# Effects.net
KiCad netlist of a schematic drawn in Altium Designer
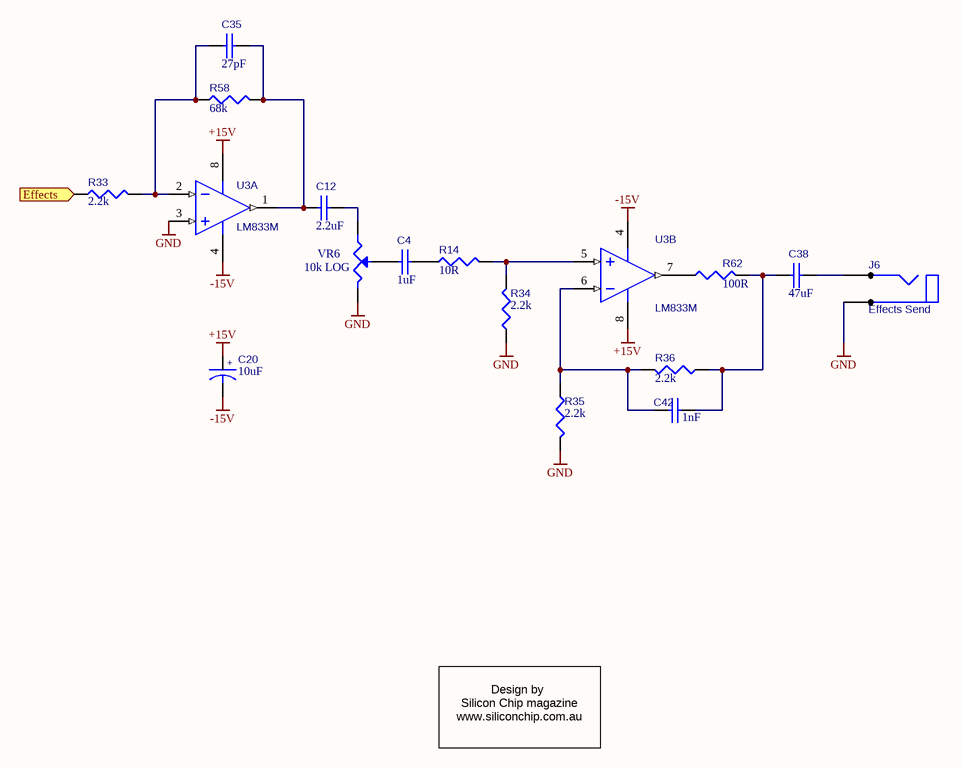
[diagram p0: Effects.SchDoc]

(export (version "E")
  (design (tool "Eeschema 10.0.6"))
  (components
    (comp (ref "C4")
      (value "1uF")
      (footprint "RB.2/.4-NP")
      (description "Capacitor")
      (libsource (lib "*") (part "CAP"))
    )
    (comp (ref "C12")
      (value "2.2uF")
      (footprint "RB.2/.4-NP")
      (description "Capacitor")
      (libsource (lib "*") (part "CAP"))
    )
    (comp (ref "C20")
      (value "10uF")
      (footprint "RB.2/.4")
      (description "Bi-Polar Capacitor")
      (libsource (lib "*") (part "CAPACITOR POL"))
    )
    (comp (ref "C35")
      (value "27pF")
      (footprint "RAD0.2")
      (description "Capacitor")
      (libsource (lib "*") (part "CAP"))
    )
    (comp (ref "C38")
      (value "47uF")
      (footprint "RB.2/.4-NP")
      (description "Capacitor")
      (libsource (lib "*") (part "CAP"))
    )
    (comp (ref "C42")
      (value "1nF")
      (footprint "RAD0.2")
      (description "Capacitor")
      (libsource (lib "*") (part "CAP"))
    )
    (comp (ref "J6")
      (value "Effects Send")
      (footprint "JACK-6.25MM")
      (libsource (lib "*") (part "PHONEJACK MONO"))
    )
    (comp (ref "R14")
      (value "10R")
      (footprint "AXIAL0.4")
      (description "Resistor")
      (libsource (lib "*") (part "RES1"))
    )
    (comp (ref "R33")
      (value "2.2k")
      (footprint "AXIAL0.4")
      (description "Resistor")
      (libsource (lib "*") (part "RES1"))
    )
    (comp (ref "R34")
      (value "2.2k")
      (footprint "AXIAL0.4")
      (description "Resistor")
      (libsource (lib "") (part "RES1_2"))
    )
    (comp (ref "R35")
      (value "2.2k")
      (footprint "AXIAL0.4")
      (description "Resistor")
      (libsource (lib "") (part "RES1_3"))
    )
    (comp (ref "R36")
      (value "2.2k")
      (footprint "AXIAL0.4")
      (description "Resistor")
      (libsource (lib "") (part "RES1_1"))
    )
    (comp (ref "R58")
      (value "68k")
      (footprint "AXIAL0.4")
      (description "Resistor")
      (libsource (lib "*") (part "RES1"))
    )
    (comp (ref "R62")
      (value "100R")
      (footprint "AXIAL0.4")
      (description "Resistor")
      (libsource (lib "*") (part "RES1"))
    )
    (comp (ref "U3")
      (value "LM833M")
      (footprint "DIP8")
      (description "Fast Settling Dual Operational Amplifier")
      (libsource (lib "*") (part "LM833M"))
    )
    (comp (ref "VR6")
      (value "10k LOG")
      (footprint "POT - 24MM")
      (description "Potentiometer")
      (libsource (lib "*") (part "POT1"))
    )
  )
  (nets
    (net (code "1") (name "+15V") (class "Default")
      (node (ref "C20") (pin "1") (pinfunction "1_1") (pintype "passive"))
      (node (ref "U3") (pin "8") (pinfunction "V+_8") (pintype "power_in"))
    )
    (net (code "2") (name "-15V") (class "Default")
      (node (ref "C20") (pin "2") (pinfunction "2_2") (pintype "passive"))
      (node (ref "U3") (pin "4") (pinfunction "V-_4") (pintype "power_in"))
    )
    (net (code "3") (name "/Effects") (class "Default")
      (node (ref "R33") (pin "1") (pinfunction "1_1") (pintype "passive"))
    )
    (net (code "4") (name "GND") (class "Default")
      (node (ref "J6") (pin "3") (pinfunction "C_3") (pintype "passive"))
      (node (ref "R34") (pin "1") (pinfunction "1_1") (pintype "passive"))
      (node (ref "R35") (pin "2") (pinfunction "2_2") (pintype "passive"))
      (node (ref "U3") (pin "3") (pinfunction "IN1+_3") (pintype "input"))
      (node (ref "VR6") (pin "3") (pinfunction "3_3") (pintype "passive"))
    )
    (net (code "5") (name "Net-(C4-Pad2)") (class "Default")
      (node (ref "C4") (pin "2") (pinfunction "2_2") (pintype "passive"))
      (node (ref "R14") (pin "1") (pinfunction "1_1") (pintype "passive"))
    )
    (net (code "6") (name "Net-(C12-Pad2)") (class "Default")
      (node (ref "C12") (pin "2") (pinfunction "2_2") (pintype "passive"))
      (node (ref "VR6") (pin "1") (pinfunction "1_1") (pintype "passive"))
    )
    (net (code "7") (name "Net-(C38-Pad1)") (class "Default")
      (node (ref "C38") (pin "1") (pinfunction "1_1") (pintype "passive"))
      (node (ref "C42") (pin "2") (pinfunction "2_2") (pintype "passive"))
      (node (ref "R36") (pin "1") (pinfunction "1_1") (pintype "passive"))
      (node (ref "R62") (pin "2") (pinfunction "2_2") (pintype "passive"))
    )
    (net (code "8") (name "Net-(J6-A)") (class "Default")
      (node (ref "C38") (pin "2") (pinfunction "2_2") (pintype "passive"))
      (node (ref "J6") (pin "1") (pinfunction "A_1") (pintype "passive"))
    )
    (net (code "9") (name "Net-(U3A-IN1-)") (class "Default")
      (node (ref "C35") (pin "1") (pinfunction "1_1") (pintype "passive"))
      (node (ref "R33") (pin "2") (pinfunction "2_2") (pintype "passive"))
      (node (ref "R58") (pin "1") (pinfunction "1_1") (pintype "passive"))
      (node (ref "U3") (pin "2") (pinfunction "IN1-_2") (pintype "input"))
    )
    (net (code "10") (name "Net-(U3A-OUT1)") (class "Default")
      (node (ref "C12") (pin "1") (pinfunction "1_1") (pintype "passive"))
      (node (ref "C35") (pin "2") (pinfunction "2_2") (pintype "passive"))
      (node (ref "R58") (pin "2") (pinfunction "2_2") (pintype "passive"))
      (node (ref "U3") (pin "1") (pinfunction "OUT1_1") (pintype "output"))
    )
    (net (code "11") (name "Net-(U3B-IN2+)") (class "Default")
      (node (ref "R14") (pin "2") (pinfunction "2_2") (pintype "passive"))
      (node (ref "R34") (pin "2") (pinfunction "2_2") (pintype "passive"))
      (node (ref "U3") (pin "5") (pinfunction "IN2+_5") (pintype "input"))
    )
    (net (code "12") (name "Net-(U3B-IN2-)") (class "Default")
      (node (ref "C42") (pin "1") (pinfunction "1_1") (pintype "passive"))
      (node (ref "R35") (pin "1") (pinfunction "1_1") (pintype "passive"))
      (node (ref "R36") (pin "2") (pinfunction "2_2") (pintype "passive"))
      (node (ref "U3") (pin "6") (pinfunction "IN2-_6") (pintype "input"))
    )
    (net (code "13") (name "Net-(U3B-OUT2)") (class "Default")
      (node (ref "R62") (pin "1") (pinfunction "1_1") (pintype "passive"))
      (node (ref "U3") (pin "7") (pinfunction "OUT2_7") (pintype "output"))
    )
    (net (code "14") (name "Net-(VR6-W)") (class "Default")
      (node (ref "C4") (pin "1") (pinfunction "1_1") (pintype "passive"))
      (node (ref "VR6") (pin "2") (pinfunction "W_2") (pintype "passive"))
    )
  )
)
